# Low_Power_Brushed_Motor_Controller_Schem.net
KiCad netlist of a schematic drawn in Altium Designer
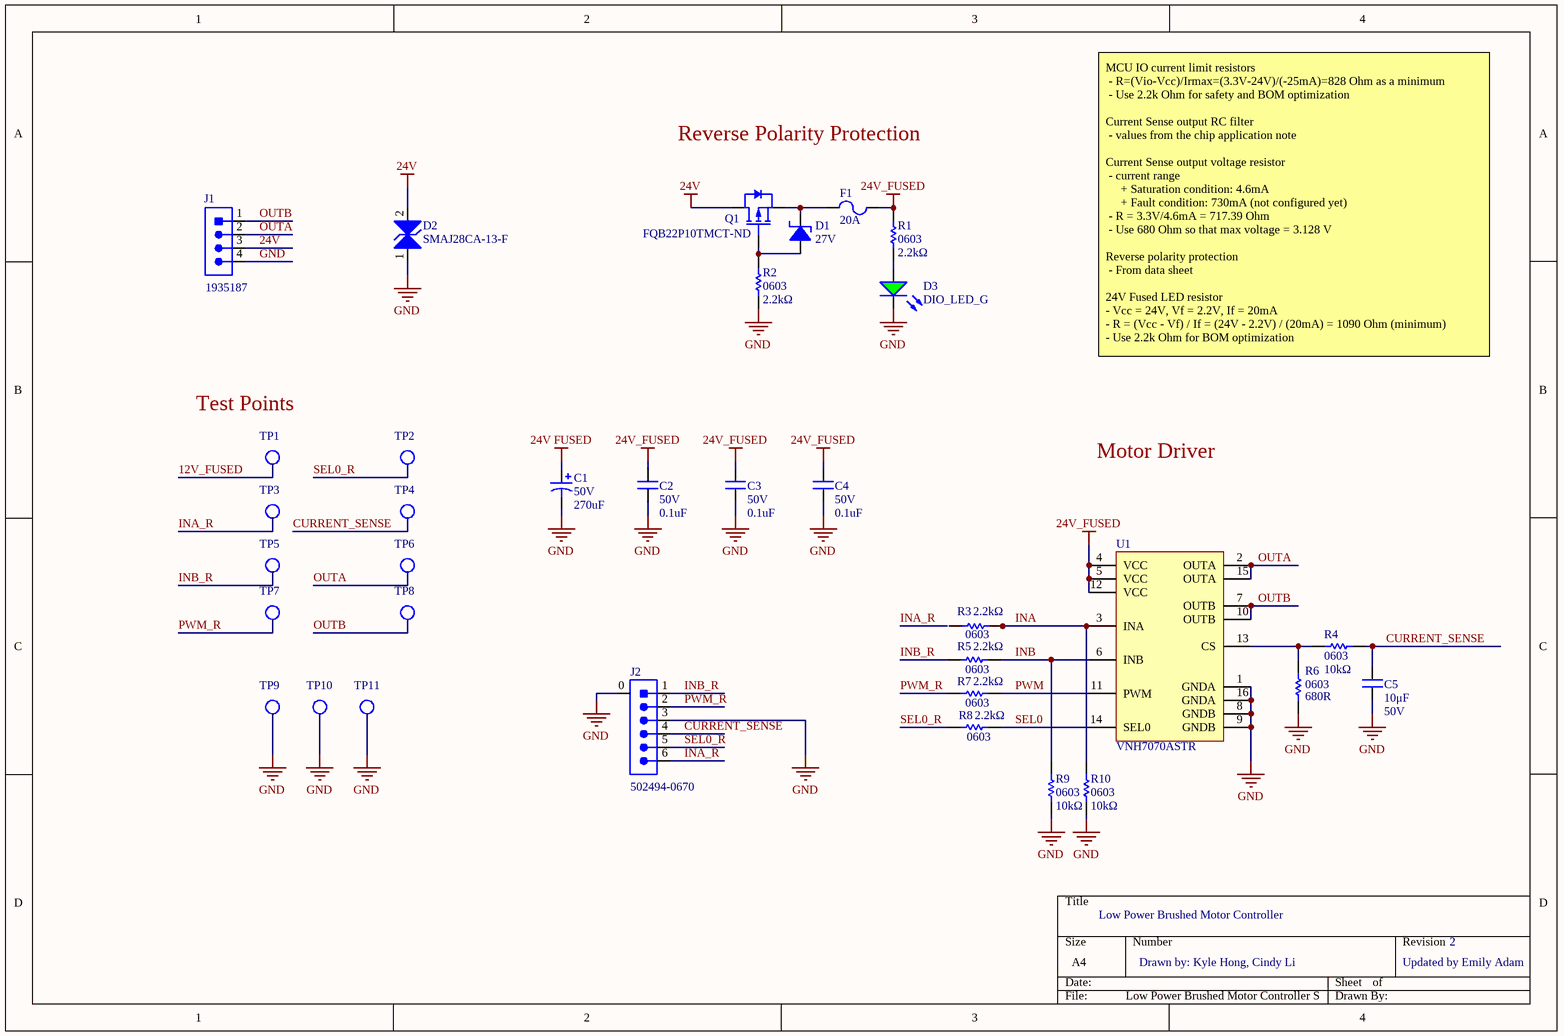
[diagram p0: Low Power Brushed Motor Controller Schematic.SchDoc]

(export (version "E")
  (design (tool "Eeschema 10.0.6"))
  (components
    (comp (ref "C1")
      (value "CAP_270uF_50V_ALUM")
      (footprint "RADIAL_PANASONIC_G")
      (description "CAP ALUM 270UF 20% 50V RADIAL")
      (fields
        (field (name "TOLERANCE") "20%")
        (field (name "VOLTAGE RATING") "50V")
        (field (name "CAPACITANCE") "270uF")
      )
      (libsource (lib "UWRT_Schematic_Library_2020") (part "CAP_270uF_50V_ALUM"))
    )
    (comp (ref "C2")
      (value "0.1uF")
      (footprint "CAPC0603(1608)55_N")
      (description "CAP CER 0.1UF 50V X7R 0603")
      (fields (field (name "VOLTAGE RATING") "50V") (field (name "Comment") "CAP_0.1uF_50V_0603"))
      (libsource (lib "UWRT_Schematic_Library_2020") (part "CAP_0.1uF_50V_0603"))
    )
    (comp (ref "C3")
      (value "0.1uF")
      (footprint "CAPC0603(1608)55_N")
      (description "CAP CER 0.1UF 50V X7R 0603")
      (fields (field (name "VOLTAGE RATING") "50V") (field (name "Comment") "CAP_0.1uF_50V_0603"))
      (libsource (lib "UWRT_Schematic_Library_2020") (part "CAP_0.1uF_50V_0603"))
    )
    (comp (ref "C4")
      (value "0.1uF")
      (footprint "CAPC0603(1608)55_N")
      (description "CAP CER 0.1UF 50V X7R 0603")
      (fields (field (name "VOLTAGE RATING") "50V") (field (name "Comment") "CAP_0.1uF_50V_0603"))
      (libsource (lib "UWRT_Schematic_Library_2020") (part "CAP_0.1uF_50V_0603"))
    )
    (comp (ref "C5")
      (value "10μF")
      (footprint "CAPC1206(3216)")
      (description "CAP CER 10UF 50V X5R 1206")
      (fields (field (name "VOLTAGE RATING") "50V") (field (name "Comment") "10uF"))
      (libsource (lib "UWRT_Schematic_Library_2020") (part "CAP_10uF_50V_1206"))
    )
    (comp (ref "D1")
      (value "DIO_ZENER_27V")
      (footprint "SOT23-3")
      (description "DIODE ZENER 27V 250MW SOT23")
      (fields (field (name "TOLERANCE") "5%") (field (name "WORKING VOLTAGE") "27V"))
      (libsource (lib "UWRT_Schematic_Library_2020") (part "DIO_ZENER_27V"))
    )
    (comp (ref "D2")
      (value "TVS_DIODE_BIDIR_28V")
      (footprint "DO-214AC")
      (description "TVS DIODE 28V 45.4V SMA")
      (fields (field (name "MANUFACTURER PART NUMBER 1") "SMAJ28CA-13-F"))
      (libsource (lib "UWRT_Schematic_Library_2020") (part "TVS_DIODE_BIDIR_28V"))
    )
    (comp (ref "D3")
      (value "DIO_LED_G")
      (footprint "LED_0805_LINE")
      (description "LED GREEN DIFFUSED 0805 SMD")
      (fields (field (name "MPN") "LG R971-KN-1") (field (name "MANUFACTURER") "OSRAM"))
      (libsource (lib "UWRT_Schematic_Library_2020") (part "DIO_LED_G"))
    )
    (comp (ref "F1")
      (value "FUSE_20A_1206")
      (footprint "FUSE_1206")
      (fields (field (name "CURRENT RATING") "20A"))
      (libsource (lib "UWRT_Schematic_Library_2020") (part "FUSE_20A_1206"))
    )
    (comp (ref "J1")
      (value "CON_4M_TERM")
      (footprint "UWRT_Footprint_Library_2020:1935187")
      (description "TERM BLK 4POS SIDE ENTRY 5MM PCB")
      (fields (field (name "MANUFACTURER PART NUMBER 1") "1935187") (field (name "VOLTAGE") "300V"))
      (libsource (lib "UWRT_Schematic_Library_2020") (part "CON_4M_TERM"))
    )
    (comp (ref "J2")
      (value "CON_6M_SM_RA")
      (footprint "MOLEX-5024940670")
      (description "CONN HEADER SMD RIGHT ANGLE 2MM PITCH")
      (fields (field (name "MANUFACTURER PART NUMBER 1") "502494-0670"))
      (libsource (lib "UWRT_Schematic_Library_2020") (part "CON_6M_SM_RA"))
    )
    (comp (ref "Q1")
      (value "PMOS_100V_22A")
      (footprint "SOT404")
      (description "MOSFET P-CH 100V 22A D2PAK")
      (fields (field (name "SUPPLIER PART NUMBER 1") "FQB22P10TMCT-ND"))
      (libsource (lib "UWRT_Schematic_Library_2020") (part "PMOS_100V_22A"))
    )
    (comp (ref "R1")
      (value "2.2kΩ")
      (footprint "RESC0603(1608)_N")
      (description "RES SMD 2.2K OHM 1% 1/10W 0603")
      (fields
        (field (name "TOLERANCE") "1%")
        (field (name "CASE CODE (IMPERIAL)") "0603")
        (field (name "Comment") "RES_2.2kΩ_0603")
      )
      (libsource (lib "UWRT_Schematic_Library_2020") (part "RES_2.2kΩ_0603"))
    )
    (comp (ref "R2")
      (value "2.2kΩ")
      (footprint "RESC0603(1608)_N")
      (description "RES SMD 2.2K OHM 1% 1/10W 0603")
      (fields
        (field (name "TOLERANCE") "1%")
        (field (name "CASE CODE (IMPERIAL)") "0603")
        (field (name "Comment") "RES_2.2kΩ_0603")
      )
      (libsource (lib "UWRT_Schematic_Library_2020") (part "RES_2.2kΩ_0603"))
    )
    (comp (ref "R3")
      (value "2.2kΩ")
      (footprint "RESC0603(1608)_N")
      (description "RES SMD 2.2K OHM 1% 1/10W 0603")
      (fields
        (field (name "TOLERANCE") "1%")
        (field (name "CASE CODE (IMPERIAL)") "0603")
        (field (name "Comment") "RES_2.2kΩ_0603")
      )
      (libsource (lib "UWRT_Schematic_Library_2020") (part "RES_2.2kΩ_0603"))
    )
    (comp (ref "R4")
      (value "10kΩ")
      (footprint "RESC0603(1608)_N")
      (description "RES SMD 10K OHM 5% 1/10W 0603")
      (fields
        (field (name "TOLERANCE") "5%")
        (field (name "CASE CODE (IMPERIAL)") "0603")
        (field (name "Comment") "RES_10kΩ_0603")
      )
      (libsource (lib "UWRT_Schematic_Library_2020") (part "RES_10kΩ_0603"))
    )
    (comp (ref "R5")
      (value "2.2kΩ")
      (footprint "RESC0603(1608)_N")
      (description "RES SMD 2.2K OHM 1% 1/10W 0603")
      (fields
        (field (name "TOLERANCE") "1%")
        (field (name "CASE CODE (IMPERIAL)") "0603")
        (field (name "Comment") "RES_2.2kΩ_0603")
      )
      (libsource (lib "UWRT_Schematic_Library_2020") (part "RES_2.2kΩ_0603"))
    )
    (comp (ref "R6")
      (value "RES_680R_0603")
      (footprint "RESC0603(1608)_N")
      (description "RES SMD 680 OHM 5% 0.1W 0603")
      (fields
        (field (name "TOLERANCE") "5%")
        (field (name "CASE/PACKAGE") "0603")
        (field (name "RESISTANCE") "680R")
      )
      (libsource (lib "UWRT_Schematic_Library_2020") (part "RES_680R_0603"))
    )
    (comp (ref "R7")
      (value "2.2kΩ")
      (footprint "RESC0603(1608)_N")
      (description "RES SMD 2.2K OHM 1% 1/10W 0603")
      (fields
        (field (name "TOLERANCE") "1%")
        (field (name "CASE CODE (IMPERIAL)") "0603")
        (field (name "Comment") "RES_2.2kΩ_0603")
      )
      (libsource (lib "UWRT_Schematic_Library_2020") (part "RES_2.2kΩ_0603"))
    )
    (comp (ref "R8")
      (value "2.2kΩ")
      (footprint "RESC0603(1608)_N")
      (description "RES SMD 2.2K OHM 1% 1/10W 0603")
      (fields
        (field (name "TOLERANCE") "1%")
        (field (name "CASE CODE (IMPERIAL)") "0603")
        (field (name "Comment") "RES_2.2kΩ_0603")
      )
      (libsource (lib "UWRT_Schematic_Library_2020") (part "RES_2.2kΩ_0603"))
    )
    (comp (ref "R9")
      (value "10kΩ")
      (footprint "RESC0603(1608)_N")
      (description "RES SMD 10K OHM 5% 1/10W 0603")
      (fields
        (field (name "TOLERANCE") "5%")
        (field (name "CASE CODE (IMPERIAL)") "0603")
        (field (name "Comment") "RES_10kΩ_0603")
      )
      (libsource (lib "UWRT_Schematic_Library_2020") (part "RES_10kΩ_0603"))
    )
    (comp (ref "R10")
      (value "10kΩ")
      (footprint "RESC0603(1608)_N")
      (description "RES SMD 10K OHM 5% 1/10W 0603")
      (fields
        (field (name "TOLERANCE") "5%")
        (field (name "CASE CODE (IMPERIAL)") "0603")
        (field (name "Comment") "RES_10kΩ_0603")
      )
      (libsource (lib "UWRT_Schematic_Library_2020") (part "RES_10kΩ_0603"))
    )
    (comp (ref "TP1")
      (value "TESTPOINT_LOOP")
      (footprint "TESTPOINT_LOOP")
      (description "Loop testpoint through-hole pad")
      (fields (field (name "MANUFACTURER") "Keystone Electronics"))
      (libsource (lib "UWRT_Schematic_Library_2020") (part "TESTPOINT_LOOP"))
    )
    (comp (ref "TP2")
      (value "TESTPOINT_LOOP")
      (footprint "TESTPOINT_LOOP")
      (description "Loop testpoint through-hole pad")
      (fields (field (name "MANUFACTURER") "Keystone Electronics"))
      (libsource (lib "UWRT_Schematic_Library_2020") (part "TESTPOINT_LOOP"))
    )
    (comp (ref "TP3")
      (value "TESTPOINT_LOOP")
      (footprint "TESTPOINT_LOOP")
      (description "Loop testpoint through-hole pad")
      (fields (field (name "MANUFACTURER") "Keystone Electronics"))
      (libsource (lib "UWRT_Schematic_Library_2020") (part "TESTPOINT_LOOP"))
    )
    (comp (ref "TP4")
      (value "TESTPOINT_LOOP")
      (footprint "TESTPOINT_LOOP")
      (description "Loop testpoint through-hole pad")
      (fields (field (name "MANUFACTURER") "Keystone Electronics"))
      (libsource (lib "UWRT_Schematic_Library_2020") (part "TESTPOINT_LOOP"))
    )
    (comp (ref "TP5")
      (value "TESTPOINT_LOOP")
      (footprint "TESTPOINT_LOOP")
      (description "Loop testpoint through-hole pad")
      (fields (field (name "MANUFACTURER") "Keystone Electronics"))
      (libsource (lib "UWRT_Schematic_Library_2020") (part "TESTPOINT_LOOP"))
    )
    (comp (ref "TP6")
      (value "TESTPOINT_LOOP")
      (footprint "TESTPOINT_LOOP")
      (description "Loop testpoint through-hole pad")
      (fields (field (name "MANUFACTURER") "Keystone Electronics"))
      (libsource (lib "UWRT_Schematic_Library_2020") (part "TESTPOINT_LOOP"))
    )
    (comp (ref "TP7")
      (value "TESTPOINT_LOOP")
      (footprint "TESTPOINT_LOOP")
      (description "Loop testpoint through-hole pad")
      (fields (field (name "MANUFACTURER") "Keystone Electronics"))
      (libsource (lib "UWRT_Schematic_Library_2020") (part "TESTPOINT_LOOP"))
    )
    (comp (ref "TP8")
      (value "TESTPOINT_LOOP")
      (footprint "TESTPOINT_LOOP")
      (description "Loop testpoint through-hole pad")
      (fields (field (name "MANUFACTURER") "Keystone Electronics"))
      (libsource (lib "UWRT_Schematic_Library_2020") (part "TESTPOINT_LOOP"))
    )
    (comp (ref "TP9")
      (value "TESTPOINT_LOOP")
      (footprint "TESTPOINT_LOOP")
      (description "Loop testpoint through-hole pad")
      (fields (field (name "MANUFACTURER") "Keystone Electronics"))
      (libsource (lib "UWRT_Schematic_Library_2020") (part "TESTPOINT_LOOP"))
    )
    (comp (ref "TP10")
      (value "TESTPOINT_LOOP")
      (footprint "TESTPOINT_LOOP")
      (description "Loop testpoint through-hole pad")
      (fields (field (name "MANUFACTURER") "Keystone Electronics"))
      (libsource (lib "UWRT_Schematic_Library_2020") (part "TESTPOINT_LOOP"))
    )
    (comp (ref "TP11")
      (value "TESTPOINT_LOOP")
      (footprint "TESTPOINT_LOOP")
      (description "Loop testpoint through-hole pad")
      (fields (field (name "MANUFACTURER") "Keystone Electronics"))
      (libsource (lib "UWRT_Schematic_Library_2020") (part "TESTPOINT_LOOP"))
    )
    (comp (ref "U1")
      (value "IC_MOTOR_DRIVER_ST")
      (footprint "SO-16N")
      (description "IC H-BRIDGE MOTOR DRIVER 16-PINS STMicroelectronics VNH7070ASTR, SOIC")
      (fields (field (name "MANUFACTURER PART NUMBER 1") "VNH7070ASTR"))
      (libsource (lib "UWRT_Schematic_Library_2020") (part "IC_MOTOR_DRIVER_ST"))
    )
  )
  (nets
    (net (code "1") (name "/12V_FUSED") (class "Default") (node (ref "TP1") (pin "1") (pintype "passive")))
    (net (code "2") (name "/CURRENT_SENSE") (class "Default")
      (node (ref "C5") (pin "2") (pinfunction "2_2") (pintype "passive"))
      (node (ref "J2") (pin "4") (pinfunction "4_4") (pintype "passive"))
      (node (ref "R4") (pin "1") (pinfunction "1_1") (pintype "passive"))
      (node (ref "TP4") (pin "1") (pintype "passive"))
    )
    (net (code "3") (name "/INA") (class "Default")
      (node (ref "R10") (pin "2") (pinfunction "2_2") (pintype "passive"))
      (node (ref "R3") (pin "1") (pinfunction "1_1") (pintype "passive"))
      (node (ref "U1") (pin "3") (pinfunction "INA_3") (pintype "passive"))
    )
    (net (code "4") (name "/INA_R") (class "Default")
      (node (ref "J2") (pin "6") (pinfunction "6_6") (pintype "passive"))
      (node (ref "TP3") (pin "1") (pintype "passive"))
    )
    (net (code "5") (name "/INB") (class "Default")
      (node (ref "R5") (pin "2") (pinfunction "2_2") (pintype "passive"))
      (node (ref "R9") (pin "2") (pinfunction "2_2") (pintype "passive"))
      (node (ref "U1") (pin "6") (pinfunction "INB_6") (pintype "passive"))
    )
    (net (code "6") (name "/INB_R") (class "Default")
      (node (ref "J2") (pin "1") (pinfunction "1_1") (pintype "passive"))
      (node (ref "R5") (pin "1") (pinfunction "1_1") (pintype "passive"))
      (node (ref "TP5") (pin "1") (pintype "passive"))
    )
    (net (code "7") (name "/OUTA") (class "Default")
      (node (ref "J1") (pin "2") (pinfunction "2_2") (pintype "passive"))
      (node (ref "TP6") (pin "1") (pintype "passive"))
      (node (ref "U1") (pin "15") (pinfunction "OUTA_15") (pintype "passive"))
      (node (ref "U1") (pin "2") (pinfunction "OUTA_2") (pintype "passive"))
    )
    (net (code "8") (name "/OUTB") (class "Default")
      (node (ref "J1") (pin "1") (pinfunction "1_1") (pintype "passive"))
      (node (ref "TP8") (pin "1") (pintype "passive"))
      (node (ref "U1") (pin "10") (pinfunction "OUTB_10") (pintype "passive"))
      (node (ref "U1") (pin "7") (pinfunction "OUTB_7") (pintype "passive"))
    )
    (net (code "9") (name "/PWM") (class "Default")
      (node (ref "R7") (pin "2") (pinfunction "2_2") (pintype "passive"))
      (node (ref "U1") (pin "11") (pinfunction "PWM_11") (pintype "passive"))
    )
    (net (code "10") (name "/PWM_R") (class "Default")
      (node (ref "J2") (pin "2") (pinfunction "2_2") (pintype "passive"))
      (node (ref "R7") (pin "1") (pinfunction "1_1") (pintype "passive"))
      (node (ref "TP7") (pin "1") (pintype "passive"))
    )
    (net (code "11") (name "/SEL0") (class "Default")
      (node (ref "R8") (pin "2") (pinfunction "2_2") (pintype "passive"))
      (node (ref "U1") (pin "14") (pinfunction "SEL0_14") (pintype "passive"))
    )
    (net (code "12") (name "/SEL0_R") (class "Default")
      (node (ref "J2") (pin "5") (pinfunction "5_5") (pintype "passive"))
      (node (ref "R8") (pin "1") (pinfunction "1_1") (pintype "passive"))
      (node (ref "TP2") (pin "1") (pintype "passive"))
    )
    (net (code "13") (name "24V") (class "Default")
      (node (ref "D2") (pin "2") (pinfunction "2_2") (pintype "passive"))
      (node (ref "J1") (pin "3") (pinfunction "3_3") (pintype "passive"))
      (node (ref "Q1") (pin "1") (pinfunction "Drain_1") (pintype "passive"))
    )
    (net (code "14") (name "24V FUSED") (class "Default")
      (node (ref "C1") (pin "1") (pinfunction "1_1") (pintype "passive"))
    )
    (net (code "15") (name "24V_FUSED") (class "Default")
      (node (ref "C2") (pin "2") (pinfunction "2_2") (pintype "passive"))
      (node (ref "C3") (pin "2") (pinfunction "2_2") (pintype "passive"))
      (node (ref "C4") (pin "1") (pinfunction "1_1") (pintype "passive"))
      (node (ref "F1") (pin "2") (pinfunction "2_2") (pintype "passive"))
      (node (ref "R1") (pin "2") (pinfunction "2_2") (pintype "passive"))
      (node (ref "U1") (pin "12") (pinfunction "VCC_12") (pintype "power_in"))
      (node (ref "U1") (pin "4") (pinfunction "VCC_4") (pintype "power_in"))
      (node (ref "U1") (pin "5") (pinfunction "VCC_5") (pintype "power_in"))
    )
    (net (code "16") (name "GND") (class "Default")
      (node (ref "C1") (pin "2") (pinfunction "2_2") (pintype "passive"))
      (node (ref "C2") (pin "1") (pinfunction "1_1") (pintype "passive"))
      (node (ref "C3") (pin "1") (pinfunction "1_1") (pintype "passive"))
      (node (ref "C4") (pin "2") (pinfunction "2_2") (pintype "passive"))
      (node (ref "C5") (pin "1") (pinfunction "1_1") (pintype "passive"))
      (node (ref "D2") (pin "1") (pinfunction "1_1") (pintype "passive"))
      (node (ref "D3") (pin "2") (pinfunction "K_2") (pintype "passive"))
      (node (ref "J1") (pin "4") (pinfunction "4_4") (pintype "passive"))
      (node (ref "J2") (pin "0") (pinfunction "0_0") (pintype "passive"))
      (node (ref "J2") (pin "3") (pinfunction "3_3") (pintype "passive"))
      (node (ref "R10") (pin "1") (pinfunction "1_1") (pintype "passive"))
      (node (ref "R2") (pin "1") (pinfunction "1_1") (pintype "passive"))
      (node (ref "R6") (pin "1") (pinfunction "1_1") (pintype "passive"))
      (node (ref "R9") (pin "1") (pinfunction "1_1") (pintype "passive"))
      (node (ref "TP10") (pin "1") (pintype "passive"))
      (node (ref "TP11") (pin "1") (pintype "passive"))
      (node (ref "TP9") (pin "1") (pintype "passive"))
      (node (ref "U1") (pin "1") (pinfunction "GNDA_1") (pintype "power_in"))
      (node (ref "U1") (pin "16") (pinfunction "GNDA_16") (pintype "power_in"))
      (node (ref "U1") (pin "8") (pinfunction "GNDB_8") (pintype "power_in"))
      (node (ref "U1") (pin "9") (pinfunction "GNDB_9") (pintype "power_in"))
    )
    (net (code "17") (name "Net-(D1-Anode)") (class "Default")
      (node (ref "D1") (pin "1") (pinfunction "Anode_1") (pintype "passive"))
      (node (ref "Q1") (pin "2") (pinfunction "Gate_2") (pintype "passive"))
      (node (ref "R2") (pin "2") (pinfunction "2_2") (pintype "passive"))
    )
    (net (code "18") (name "Net-(D1-Cathode)") (class "Default")
      (node (ref "D1") (pin "2") (pinfunction "Cathode_2") (pintype "passive"))
      (node (ref "F1") (pin "1") (pinfunction "1_1") (pintype "passive"))
      (node (ref "Q1") (pin "3") (pinfunction "Source_3") (pintype "passive"))
    )
    (net (code "19") (name "Net-(D3-A)") (class "Default")
      (node (ref "D3") (pin "1") (pinfunction "A_1") (pintype "passive"))
      (node (ref "R1") (pin "1") (pinfunction "1_1") (pintype "passive"))
    )
    (net (code "20") (name "Net-(U1-CS)") (class "Default")
      (node (ref "R4") (pin "2") (pinfunction "2_2") (pintype "passive"))
      (node (ref "R6") (pin "2") (pinfunction "2_2") (pintype "passive"))
      (node (ref "U1") (pin "13") (pinfunction "CS_13") (pintype "passive"))
    )
    (net (code "21") (name "unconnected-(R3-Pad2)") (class "Default")
      (node (ref "R3") (pin "2") (pinfunction "2_2") (pintype "passive"))
    )
  )
)
